# 1-6_connector.net
KiCad netlist of a schematic drawn in EAGLE
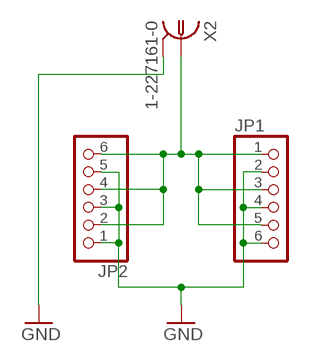
[diagram p0: schematic, sheet 1]

(export (version "E")
  (design (tool "Eeschema 10.0.6"))
  (components
    (comp (ref "JP1")
      (value "PINHD-1X6")
      (footprint "eagle-import:1X06")
      (libsource (lib "eagle-import") (part "PINHD-1X6"))
    )
    (comp (ref "JP2")
      (value "PINHD-1X6")
      (footprint "eagle-import:1X06")
      (libsource (lib "eagle-import") (part "PINHD-1X6"))
    )
    (comp (ref "X2")
      (value "1-227161-0")
      (footprint "eagle-import:AMP_227161")
      (fields (field (name "MF") "TYCO ELECTRONICS") (field (name "MPN") "1-227161"))
      (libsource (lib "eagle-import") (part "?2271611--0"))
    )
  )
  (nets
    (net (code "1") (name "GND") (class "Default")
      (node (ref "JP1") (pin "2") (pinfunction "2_2") (pintype "passive"))
      (node (ref "JP1") (pin "4") (pinfunction "4_4") (pintype "passive"))
      (node (ref "JP1") (pin "6") (pinfunction "6_6") (pintype "passive"))
      (node (ref "JP2") (pin "1") (pinfunction "1_1") (pintype "passive"))
      (node (ref "JP2") (pin "3") (pinfunction "3_3") (pintype "passive"))
      (node (ref "JP2") (pin "5") (pinfunction "5_5") (pintype "passive"))
      (node (ref "X2") (pin "2") (pinfunction "2_2") (pintype "passive"))
    )
    (net (code "2") (name "Net-(JP1-Pad1)") (class "Default")
      (node (ref "JP1") (pin "1") (pinfunction "1_1") (pintype "passive"))
      (node (ref "JP1") (pin "3") (pinfunction "3_3") (pintype "passive"))
      (node (ref "JP1") (pin "5") (pinfunction "5_5") (pintype "passive"))
      (node (ref "JP2") (pin "2") (pinfunction "2_2") (pintype "passive"))
      (node (ref "JP2") (pin "4") (pinfunction "4_4") (pintype "passive"))
      (node (ref "JP2") (pin "6") (pinfunction "6_6") (pintype "passive"))
      (node (ref "X2") (pin "1") (pinfunction "1_1") (pintype "passive"))
    )
  )
)
